# Power.net
KiCad netlist of a schematic drawn in Altium Designer
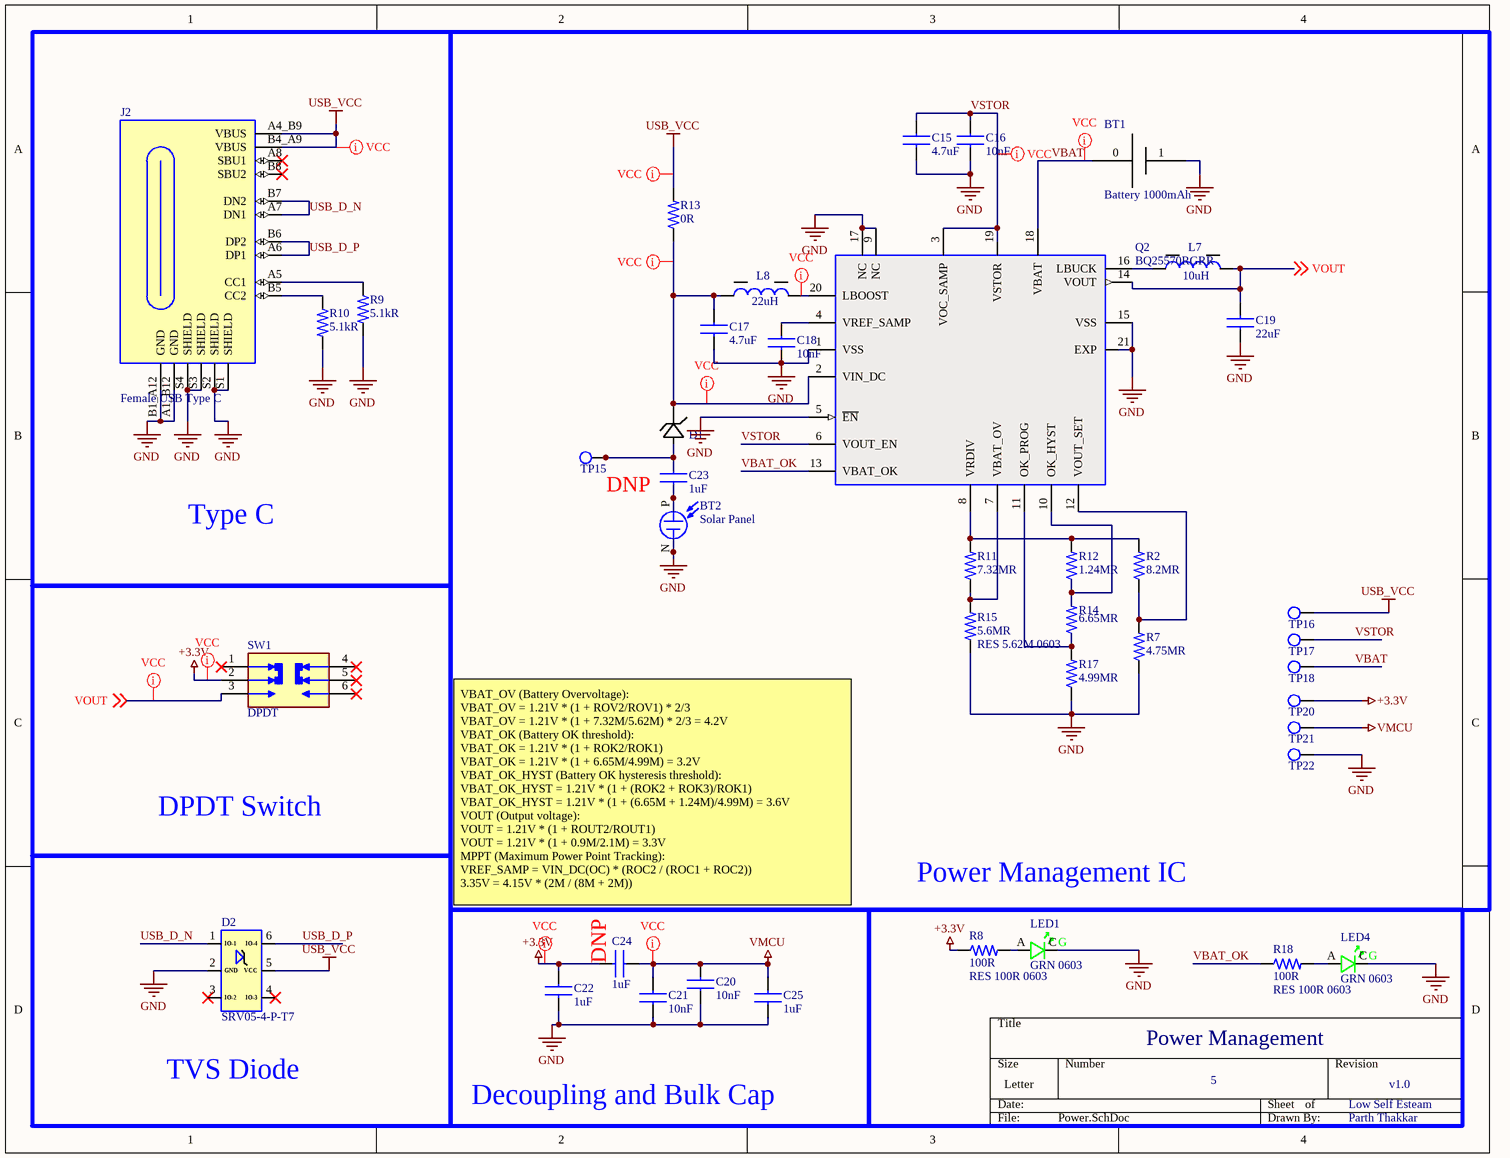
[diagram p0: Power.SchDoc]

(export (version "E")
  (design (tool "Eeschema 10.0.6"))
  (components
    (comp (ref "BT1")
      (value "Battery 1000mAh")
      (footprint "Battery")
      (description "Lithium Ion Polymer Battery - 3.7v 1200mAh ¦ Adafruit Industries 258")
      (fields
        (field (name "MANUFACTURER") "Adafruit Industries")
        (field (name "MANUFACTURER PART NUMBER") "258")
      )
      (libsource (lib "Keyboard_parts") (part "Battery 1000mAh"))
    )
    (comp (ref "BT2")
      (value "Solar Panel")
      (footprint "Solar panel")
      (description "Monocryst Solar Cell 184MW 4.15V")
      (fields (field (name "MANUFACTURER") "ANYSOLAR") (field (name "MANUFACTURER PART NUMBER") "SM141K06L"))
      (libsource (lib "Keyboard_parts") (part "Solar Panel"))
    )
    (comp (ref "C15")
      (value "4.7uF")
      (footprint "Capacitor 0603")
      (fields
        (field (name "MANUFACTURER") "Murata")
        (field (name "MANUFACTURER PART NUMBER") "GRT188R61E475KE13D")
        (field (name "Comment") "CAP 4.7uF 25V 0603")
      )
      (libsource (lib "Keyboard_parts") (part "CAP 4.7uF 25V 0603"))
    )
    (comp (ref "C16")
      (value "10nF")
      (footprint "Capacitor 0603")
      (fields
        (field (name "MANUFACTURER") "Murata")
        (field (name "MANUFACTURER PART NUMBER") "GCM188R72A103KA37D")
        (field (name "Comment") "CAP 10nF 100V 0603")
      )
      (libsource (lib "Keyboard_parts") (part "CAP 10nF 100V 0603"))
    )
    (comp (ref "C17")
      (value "4.7uF")
      (footprint "Capacitor 0603")
      (fields
        (field (name "MANUFACTURER") "Murata")
        (field (name "MANUFACTURER PART NUMBER") "GRT188R61E475KE13D")
        (field (name "Comment") "CAP 4.7uF 25V 0603")
      )
      (libsource (lib "Keyboard_parts") (part "CAP 4.7uF 25V 0603"))
    )
    (comp (ref "C18")
      (value "10nF")
      (footprint "Capacitor 0603")
      (fields
        (field (name "MANUFACTURER") "Murata")
        (field (name "MANUFACTURER PART NUMBER") "GCM188R72A103KA37D")
        (field (name "Comment") "CAP 10nF 100V 0603")
      )
      (libsource (lib "Keyboard_parts") (part "CAP 10nF 100V 0603"))
    )
    (comp (ref "C19")
      (value "22uF")
      (footprint "Capacitor 0603")
      (fields
        (field (name "MANUFACTURER") "Murata")
        (field (name "MANUFACTURER PART NUMBER") "GRM188R61A226ME15D")
        (field (name "TOLERANCE") "20 %")
      )
      (libsource (lib "Keyboard_parts") (part "CAP 22uF 6.3V 0603"))
    )
    (comp (ref "C20")
      (value "10nF")
      (footprint "Capacitor 0603")
      (fields
        (field (name "MANUFACTURER") "Murata")
        (field (name "MANUFACTURER PART NUMBER") "GCM188R72A103KA37D")
        (field (name "Comment") "CAP 0.1uF 100V 0603")
      )
      (libsource (lib "Keyboard_parts") (part "CAP 0.1uF 100V 0603"))
    )
    (comp (ref "C21")
      (value "10nF")
      (footprint "Capacitor 0603")
      (fields
        (field (name "MANUFACTURER") "Murata")
        (field (name "MANUFACTURER PART NUMBER") "GCM188R72A103KA37D")
        (field (name "Comment") "CAP 0.1uF 100V 0603")
      )
      (libsource (lib "Keyboard_parts") (part "CAP 0.1uF 100V 0603"))
    )
    (comp (ref "C22")
      (value "1uF")
      (footprint "CAPACITOR 0805")
      (description "Multilayer Ceramic Capacitor, 1 uF, 10 V, ± 20%, X5R, 0201 [0603 Metric]")
      (fields
        (field (name "MANUFACTURER") "Murata")
        (field (name "MANUFACTURER PART NUMBER") "GRM033R61A105ME15D")
      )
      (libsource (lib "Keyboard_parts") (part "CAP 47uF 10V 0805"))
    )
    (comp (ref "C23")
      (value "1uF")
      (footprint "CAPACITOR 0805")
      (description "Multilayer Ceramic Capacitor, 1 uF, 10 V, ± 20%, X5R, 0201 [0603 Metric]")
      (fields
        (field (name "MANUFACTURER") "Murata")
        (field (name "MANUFACTURER PART NUMBER") "GRM033R61A105ME15D")
      )
      (libsource (lib "Keyboard_parts") (part "CAP 47uF 10V 0805"))
    )
    (comp (ref "C24")
      (value "1uF")
      (footprint "CAPACITOR 0805")
      (description "Multilayer Ceramic Capacitor, 1 uF, 10 V, ± 20%, X5R, 0201 [0603 Metric]")
      (fields
        (field (name "MANUFACTURER") "Murata")
        (field (name "MANUFACTURER PART NUMBER") "GRM033R61A105ME15D")
      )
      (libsource (lib "Keyboard_parts") (part "CAP 47uF 10V 0805"))
    )
    (comp (ref "C25")
      (value "1uF")
      (footprint "CAPACITOR 0805")
      (description "Multilayer Ceramic Capacitor, 1 uF, 10 V, ± 20%, X5R, 0201 [0603 Metric]")
      (fields
        (field (name "MANUFACTURER") "Murata")
        (field (name "MANUFACTURER PART NUMBER") "GRM033R61A105ME15D")
      )
      (libsource (lib "Keyboard_parts") (part "CAP 47uF 10V 0805"))
    )
    (comp (ref "D1")
      (value "Diode Schottky")
      (footprint "Diode Schottky")
      (description "Rectifier Diode, Schottky, 2 Element, 0.2A, 30V V(RRM), Silicon")
      (fields (field (name "MANUFACTURER") "Good-Ark") (field (name "MANUFACTURER PART NUMBER") "BAT54C"))
      (libsource (lib "Keyboard_parts") (part "Diode Schottky"))
    )
    (comp (ref "D2")
      (value "SRV05-4-P-T7")
      (footprint "TVS")
      (description "Trans Voltage Suppressor Diode, 5V V(RWM), Unidirectional, 1 Element, Silicon")
      (fields (field (name "MANUFACTURER") "MCC") (field (name "MANUFACTURER PART NUMBER") "SRV05-4L-TP"))
      (libsource (lib "Keyboard_parts") (part "TVS_Diode"))
    )
    (comp (ref "J2")
      (value "Female USB Type C")
      (footprint "Type C")
      (fields (field (name "MANUFACTURER PART NUMBER") "USB4125-GF-A_REVA2"))
      (libsource (lib "Keyboard_parts") (part "USB-C Power Connector"))
    )
    (comp (ref "L7")
      (value "IND 10uH 1111")
      (footprint "IND 10uH (1x3.2)")
      (description "General Purpose Inductor, 10uH, 30%, 1 Element, Ferrite-Core, SMD, 1111")
      (fields
        (field (name "MANUFACTURER") "Wurth Electronics")
        (field (name "MANUFACTURER PART NUMBER") "744029100")
        (field (name "INDUCTANCE-NOM (L)") "10uH")
      )
      (libsource (lib "Keyboard_parts") (part "IND 10uH 1111"))
    )
    (comp (ref "L8")
      (value "IND 22uH 1515")
      (footprint "IND 22uH (1.6x4.3)")
      (description "General Purpose Inductor, 22uH, 30%, 1 Element, Ferrite-Core, SMD, 1515")
      (fields
        (field (name "MANUFACTURER") "Wurth Electronics")
        (field (name "MANUFACTURER PART NUMBER") "744031220")
        (field (name "INDUCTANCE-NOM (L)") "22uH")
      )
      (libsource (lib "Keyboard_parts") (part "IND 22uH 1515"))
    )
    (comp (ref "LED1")
      (value "GRN 0603")
      (footprint "LED 0603")
      (description "LED, 0603, GREEN, 430MCD, 520NM")
      (fields
        (field (name "MANUFACTURER") "Wurth Electronics")
        (field (name "MANUFACTURER PART NUMBER") "150060GS75000")
      )
      (libsource (lib "Keyboard_parts") (part "LED Green 0603"))
    )
    (comp (ref "LED4")
      (value "GRN 0603")
      (footprint "LED 0603")
      (description "LED, 0603, GREEN, 430MCD, 520NM")
      (fields
        (field (name "MANUFACTURER") "Wurth Electronics")
        (field (name "MANUFACTURER PART NUMBER") "150060GS75000")
      )
      (libsource (lib "Keyboard_parts") (part "LED Green 0603"))
    )
    (comp (ref "Q2")
      (value "BQ25570RGRR")
      (footprint "BQ25570RGRR")
      (description "Power Supply Support Circuit, Adjustable, 1 Channel, PQCC20")
      (fields (field (name "MANUFACTURER") "Texas Instruments"))
      (libsource (lib "Keyboard_parts") (part "BQ25570RGRR"))
    )
    (comp (ref "R2")
      (value "8.2MR")
      (footprint "Resistor 0603")
      (fields
        (field (name "MANUFACTURER") "Yageo")
        (field (name "MANUFACTURER PART NUMBER") "RC0603JR-078M2L")
        (field (name "TOLERANCE") "5%")
      )
      (libsource (lib "Keyboard_parts") (part "RES 8.2M 0603"))
    )
    (comp (ref "R7")
      (value "4.75MR")
      (footprint "Resistor 0603")
      (fields
        (field (name "MANUFACTURER") "Yageo")
        (field (name "MANUFACTURER PART NUMBER") "RC0603FR-074M75L")
        (field (name "TOLERANCE") "1%")
      )
      (libsource (lib "Keyboard_parts") (part "RES 4.75M 0603"))
    )
    (comp (ref "R8")
      (value "RES 100R 0603")
      (footprint "Resistor 0603")
      (fields
        (field (name "MANUFACTURER") "Yageo")
        (field (name "MANUFACTURER PART NUMBER") "RC0603FR-07100RL")
        (field (name "TOLERANCE") "1%")
        (field (name "ALTIUM_VALUE") "100R")
      )
      (libsource (lib "Keyboard_parts") (part "RES 100R 0603"))
    )
    (comp (ref "R9")
      (value "5.1kR")
      (footprint "Resistor 0603")
      (fields
        (field (name "MANUFACTURER") "Yageo")
        (field (name "MANUFACTURER PART NUMBER") "RC0603FR-075K1L")
        (field (name "TOLERANCE") "1%")
      )
      (libsource (lib "Keyboard_parts") (part "RES 5.1K 0603"))
    )
    (comp (ref "R10")
      (value "5.1kR")
      (footprint "Resistor 0603")
      (fields
        (field (name "MANUFACTURER") "Yageo")
        (field (name "MANUFACTURER PART NUMBER") "RC0603FR-075K1L")
        (field (name "TOLERANCE") "1%")
      )
      (libsource (lib "Keyboard_parts") (part "RES 5.1K 0603"))
    )
    (comp (ref "R11")
      (value "7.32MR")
      (footprint "Resistor 0603")
      (fields
        (field (name "MANUFACTURER") "Yageo")
        (field (name "MANUFACTURER PART NUMBER") "RC0402FR-077M32L")
        (field (name "TOLERANCE") "1%")
      )
      (libsource (lib "Keyboard_parts") (part "RES 7.32M 0603"))
    )
    (comp (ref "R12")
      (value "1.24MR")
      (footprint "Resistor 0603")
      (fields
        (field (name "MANUFACTURER") "Yageo")
        (field (name "MANUFACTURER PART NUMBER") "RC0603FR-071M24L")
        (field (name "TOLERANCE") "1%")
      )
      (libsource (lib "Keyboard_parts") (part "RES 1.24M 0603"))
    )
    (comp (ref "R13")
      (value "0R")
      (footprint "Resistor 0402")
      (description "Metal Glaze/thick Film, 0.0625W, 0ohm, Surface Mount, 0402")
      (fields
        (field (name "MANUFACTURER") "Yageo")
        (field (name "MANUFACTURER PART NUMBER") "RC0402JR-070RL")
      )
      (libsource (lib "Keyboard_parts") (part "RES 0R 0402"))
    )
    (comp (ref "R14")
      (value "6.65MR")
      (footprint "Resistor 0603")
      (fields
        (field (name "MANUFACTURER") "Vishay")
        (field (name "MANUFACTURER PART NUMBER") "CRCW06036M65FKEA")
        (field (name "TOLERANCE") "1%")
      )
      (libsource (lib "Keyboard_parts") (part "RES 6.65M 0603"))
    )
    (comp (ref "R15")
      (value "RES 5.62M 0603")
      (footprint "Resistor 0603")
      (fields
        (field (name "MANUFACTURER") "Yageo")
        (field (name "MANUFACTURER PART NUMBER") "RC0603JR-075M6L")
        (field (name "TOLERANCE") "5%")
        (field (name "ALTIUM_VALUE") "5.6MR")
      )
      (libsource (lib "Keyboard_parts") (part "RES 5.62M 0603"))
    )
    (comp (ref "R17")
      (value "4.99MR")
      (footprint "Resistor 0603")
      (fields
        (field (name "MANUFACTURER") "Yageo")
        (field (name "MANUFACTURER PART NUMBER") "RC0603FR-074M99L")
        (field (name "TOLERANCE") "1%")
      )
      (libsource (lib "Keyboard_parts") (part "RES 4.99M 0603"))
    )
    (comp (ref "R18")
      (value "RES 100R 0603")
      (footprint "Resistor 0603")
      (fields
        (field (name "MANUFACTURER") "Yageo")
        (field (name "MANUFACTURER PART NUMBER") "RC0603FR-07100RL")
        (field (name "TOLERANCE") "1%")
        (field (name "ALTIUM_VALUE") "100R")
      )
      (libsource (lib "Keyboard_parts") (part "RES 100R 0603"))
    )
    (comp (ref "SW1")
      (value "DPDT")
      (footprint "DPDT")
      (description "Slide Switch, DPDT, Latched, Solder Terminal, Through Hole-right Angle")
      (fields (field (name "MANUFACTURER") "E-Switch") (field (name "MANUFACTURER PART NUMBER") "EG2208"))
      (libsource (lib "Keyboard_parts") (part "DPDT"))
    )
    (comp (ref "TP15")
      (value "Test point")
      (footprint "Test Point")
      (libsource (lib "Keyboard_parts") (part "Test point"))
    )
    (comp (ref "TP16")
      (value "Test point")
      (footprint "Test Point")
      (libsource (lib "Keyboard_parts") (part "Test point"))
    )
    (comp (ref "TP17")
      (value "Test point")
      (footprint "Test Point")
      (libsource (lib "Keyboard_parts") (part "Test point"))
    )
    (comp (ref "TP18")
      (value "Test point")
      (footprint "Test Point")
      (libsource (lib "Keyboard_parts") (part "Test point"))
    )
    (comp (ref "TP20")
      (value "Test point")
      (footprint "Test Point")
      (libsource (lib "Keyboard_parts") (part "Test point"))
    )
    (comp (ref "TP21")
      (value "Test point")
      (footprint "Test Point")
      (libsource (lib "Keyboard_parts") (part "Test point"))
    )
    (comp (ref "TP22")
      (value "Test point")
      (footprint "Test Point")
      (libsource (lib "Keyboard_parts") (part "Test point"))
    )
  )
  (nets
    (net (code "1") (name "+3.3V") (class "Default")
      (node (ref "C22") (pin "1") (pinfunction "1_1") (pintype "passive"))
      (node (ref "C24") (pin "1") (pinfunction "1_1") (pintype "passive"))
      (node (ref "R8") (pin "1") (pinfunction "1_1") (pintype "passive"))
      (node (ref "SW1") (pin "2") (pinfunction "2_2") (pintype "passive"))
      (node (ref "TP20") (pin "1") (pinfunction "1_1") (pintype "passive"))
    )
    (net (code "2") (name "/USB_D_N") (class "Default")
      (node (ref "D2") (pin "1") (pinfunction "IO-1_1") (pintype "passive"))
      (node (ref "J2") (pin "A7") (pinfunction "DN1_A7") (pintype "bidirectional"))
      (node (ref "J2") (pin "B7") (pinfunction "DN2_B7") (pintype "bidirectional"))
    )
    (net (code "3") (name "/USB_D_P") (class "Default")
      (node (ref "D2") (pin "6") (pinfunction "IO-4_6") (pintype "passive"))
      (node (ref "J2") (pin "A6") (pinfunction "DP1_A6") (pintype "bidirectional"))
      (node (ref "J2") (pin "B6") (pinfunction "DP2_B6") (pintype "bidirectional"))
    )
    (net (code "4") (name "/VBAT") (class "Default")
      (node (ref "BT1") (pin "0") (pinfunction "VCC_0") (pintype "passive"))
      (node (ref "Q2") (pin "18") (pinfunction "VBAT_18") (pintype "power_in"))
      (node (ref "TP18") (pin "1") (pinfunction "1_1") (pintype "passive"))
    )
    (net (code "5") (name "/VBAT_OK") (class "Default")
      (node (ref "Q2") (pin "13") (pinfunction "VBAT_OK_13") (pintype "passive"))
      (node (ref "R18") (pin "1") (pinfunction "1_1") (pintype "passive"))
    )
    (net (code "6") (name "/VSTOR") (class "Default")
      (node (ref "C15") (pin "1") (pinfunction "1_1") (pintype "passive"))
      (node (ref "C16") (pin "1") (pinfunction "1_1") (pintype "passive"))
      (node (ref "Q2") (pin "19") (pinfunction "VSTOR_19") (pintype "passive"))
      (node (ref "Q2") (pin "3") (pinfunction "VOC_SAMP_3") (pintype "passive"))
      (node (ref "Q2") (pin "6") (pinfunction "VOUT_EN_6") (pintype "passive"))
      (node (ref "TP17") (pin "1") (pinfunction "1_1") (pintype "passive"))
    )
    (net (code "7") (name "GND") (class "Default")
      (node (ref "BT1") (pin "1") (pinfunction "GND_1") (pintype "passive"))
      (node (ref "BT2") (pin "N") (pinfunction "N_N") (pintype "passive"))
      (node (ref "C15") (pin "2") (pinfunction "2_2") (pintype "passive"))
      (node (ref "C16") (pin "2") (pinfunction "2_2") (pintype "passive"))
      (node (ref "C17") (pin "2") (pinfunction "2_2") (pintype "passive"))
      (node (ref "C18") (pin "1") (pinfunction "1_1") (pintype "passive"))
      (node (ref "C19") (pin "2") (pinfunction "2_2") (pintype "passive"))
      (node (ref "C20") (pin "2") (pinfunction "2_2") (pintype "passive"))
      (node (ref "C21") (pin "2") (pinfunction "2_2") (pintype "passive"))
      (node (ref "C22") (pin "2") (pinfunction "2_2") (pintype "passive"))
      (node (ref "C25") (pin "2") (pinfunction "2_2") (pintype "passive"))
      (node (ref "D2") (pin "2") (pinfunction "GND_2") (pintype "passive"))
      (node (ref "J2") (pin "A1_B12") (pinfunction "GND_A1_B12") (pintype "power_in"))
      (node (ref "J2") (pin "B1_A12") (pinfunction "GND_B1_A12") (pintype "power_in"))
      (node (ref "J2") (pin "S1") (pinfunction "SHIELD_S1") (pintype "passive"))
      (node (ref "J2") (pin "S2") (pinfunction "SHIELD_S2") (pintype "passive"))
      (node (ref "J2") (pin "S3") (pinfunction "SHIELD_S3") (pintype "passive"))
      (node (ref "J2") (pin "S4") (pinfunction "SHIELD_S4") (pintype "passive"))
      (node (ref "LED1") (pin "C") (pinfunction "C_C") (pintype "passive"))
      (node (ref "LED4") (pin "C") (pinfunction "C_C") (pintype "passive"))
      (node (ref "Q2") (pin "1") (pinfunction "VSS_1") (pintype "passive"))
      (node (ref "Q2") (pin "15") (pinfunction "VSS_15") (pintype "passive"))
      (node (ref "Q2") (pin "17") (pinfunction "NC_17") (pintype "passive"))
      (node (ref "Q2") (pin "21") (pinfunction "EXP_21") (pintype "passive"))
      (node (ref "Q2") (pin "5") (pinfunction "~{EN}_5") (pintype "input"))
      (node (ref "Q2") (pin "9") (pinfunction "NC_9") (pintype "passive"))
      (node (ref "R10") (pin "2") (pinfunction "2_2") (pintype "passive"))
      (node (ref "R15") (pin "1") (pinfunction "1_1") (pintype "passive"))
      (node (ref "R17") (pin "1") (pinfunction "1_1") (pintype "passive"))
      (node (ref "R7") (pin "1") (pinfunction "1_1") (pintype "passive"))
      (node (ref "R9") (pin "2") (pinfunction "2_2") (pintype "passive"))
      (node (ref "TP22") (pin "1") (pinfunction "1_1") (pintype "passive"))
    )
    (net (code "8") (name "Net-(BT2-PadP)") (class "Default")
      (node (ref "BT2") (pin "P") (pinfunction "P_P") (pintype "passive"))
      (node (ref "C23") (pin "2") (pinfunction "2_2") (pintype "passive"))
    )
    (net (code "9") (name "Net-(C23-Pad1)") (class "Default")
      (node (ref "C23") (pin "1") (pinfunction "1_1") (pintype "passive"))
      (node (ref "D1") (pin "1") (pinfunction "1_1") (pintype "passive"))
      (node (ref "TP15") (pin "1") (pinfunction "1_1") (pintype "passive"))
    )
    (net (code "10") (name "Net-(J2-CC1)") (class "Default")
      (node (ref "J2") (pin "A5") (pinfunction "CC1_A5") (pintype "bidirectional"))
      (node (ref "R9") (pin "1") (pinfunction "1_1") (pintype "passive"))
    )
    (net (code "11") (name "Net-(J2-CC2)") (class "Default")
      (node (ref "J2") (pin "B5") (pinfunction "CC2_B5") (pintype "bidirectional"))
      (node (ref "R10") (pin "1") (pinfunction "1_1") (pintype "passive"))
    )
    (net (code "12") (name "Net-(LED1-PadA)") (class "Default")
      (node (ref "LED1") (pin "A") (pinfunction "A_A") (pintype "passive"))
      (node (ref "R8") (pin "2") (pinfunction "2_2") (pintype "passive"))
    )
    (net (code "13") (name "Net-(LED4-PadA)") (class "Default")
      (node (ref "LED4") (pin "A") (pinfunction "A_A") (pintype "passive"))
      (node (ref "R18") (pin "2") (pinfunction "2_2") (pintype "passive"))
    )
    (net (code "14") (name "Net-(Q2-LBOOST)") (class "Default")
      (node (ref "L8") (pin "2") (pinfunction "2_2") (pintype "passive"))
      (node (ref "Q2") (pin "20") (pinfunction "LBOOST_20") (pintype "power_in"))
    )
    (net (code "15") (name "Net-(Q2-LBUCK)") (class "Default")
      (node (ref "L7") (pin "1") (pinfunction "1_1") (pintype "passive"))
      (node (ref "Q2") (pin "16") (pinfunction "LBUCK_16") (pintype "power_in"))
    )
    (net (code "16") (name "Net-(Q2-OK_HYST)") (class "Default")
      (node (ref "Q2") (pin "10") (pinfunction "OK_HYST_10") (pintype "power_in"))
      (node (ref "R12") (pin "1") (pinfunction "1_1") (pintype "passive"))
      (node (ref "R14") (pin "2") (pinfunction "2_2") (pintype "passive"))
    )
    (net (code "17") (name "Net-(Q2-OK_PROG)") (class "Default")
      (node (ref "Q2") (pin "11") (pinfunction "OK_PROG_11") (pintype "power_in"))
      (node (ref "R14") (pin "1") (pinfunction "1_1") (pintype "passive"))
      (node (ref "R17") (pin "2") (pinfunction "2_2") (pintype "passive"))
    )
    (net (code "18") (name "Net-(Q2-VBAT_OV)") (class "Default")
      (node (ref "Q2") (pin "7") (pinfunction "VBAT_OV_7") (pintype "passive"))
      (node (ref "R11") (pin "1") (pinfunction "1_1") (pintype "passive"))
      (node (ref "R15") (pin "2") (pinfunction "2_2") (pintype "passive"))
    )
    (net (code "19") (name "Net-(Q2-VIN_DC)") (class "Default")
      (node (ref "C17") (pin "1") (pinfunction "1_1") (pintype "passive"))
      (node (ref "D1") (pin "3") (pinfunction "3_3") (pintype "passive"))
      (node (ref "L8") (pin "1") (pinfunction "1_1") (pintype "passive"))
      (node (ref "Q2") (pin "2") (pinfunction "VIN_DC_2") (pintype "passive"))
      (node (ref "R13") (pin "1") (pinfunction "1_1") (pintype "passive"))
    )
    (net (code "20") (name "Net-(Q2-VOUT_SET)") (class "Default")
      (node (ref "Q2") (pin "12") (pinfunction "VOUT_SET_12") (pintype "passive"))
      (node (ref "R2") (pin "1") (pinfunction "1_1") (pintype "passive"))
      (node (ref "R7") (pin "2") (pinfunction "2_2") (pintype "passive"))
    )
    (net (code "21") (name "Net-(Q2-VRDIV)") (class "Default")
      (node (ref "Q2") (pin "8") (pinfunction "VRDIV_8") (pintype "passive"))
      (node (ref "R11") (pin "2") (pinfunction "2_2") (pintype "passive"))
      (node (ref "R12") (pin "2") (pinfunction "2_2") (pintype "passive"))
      (node (ref "R2") (pin "2") (pinfunction "2_2") (pintype "passive"))
    )
    (net (code "22") (name "Net-(Q2-VREF_SAMP)") (class "Default")
      (node (ref "C18") (pin "2") (pinfunction "2_2") (pintype "passive"))
      (node (ref "Q2") (pin "4") (pinfunction "VREF_SAMP_4") (pintype "passive"))
    )
    (net (code "23") (name "USB_VCC") (class "Default")
      (node (ref "D2") (pin "5") (pinfunction "VCC_5") (pintype "passive"))
      (node (ref "J2") (pin "A4_B9") (pinfunction "VBUS_A4_B9") (pintype "power_in"))
      (node (ref "J2") (pin "B4_A9") (pinfunction "VBUS_B4_A9") (pintype "power_in"))
      (node (ref "R13") (pin "2") (pinfunction "2_2") (pintype "passive"))
      (node (ref "TP16") (pin "1") (pinfunction "1_1") (pintype "passive"))
    )
    (net (code "24") (name "VMCU") (class "Default")
      (node (ref "C20") (pin "1") (pinfunction "1_1") (pintype "passive"))
      (node (ref "C21") (pin "1") (pinfunction "1_1") (pintype "passive"))
      (node (ref "C24") (pin "2") (pinfunction "2_2") (pintype "passive"))
      (node (ref "C25") (pin "1") (pinfunction "1_1") (pintype "passive"))
      (node (ref "TP21") (pin "1") (pinfunction "1_1") (pintype "passive"))
    )
    (net (code "25") (name "VOUT") (class "Default")
      (node (ref "C19") (pin "1") (pinfunction "1_1") (pintype "passive"))
      (node (ref "L7") (pin "2") (pinfunction "2_2") (pintype "passive"))
      (node (ref "Q2") (pin "14") (pinfunction "VOUT_14") (pintype "output"))
      (node (ref "SW1") (pin "3") (pinfunction "3_3") (pintype "passive"))
    )
    (net (code "26") (name "unconnected-(D2-IO-2-Pad3)") (class "Default")
      (node (ref "D2") (pin "3") (pinfunction "IO-2_3") (pintype "passive+no_connect"))
    )
    (net (code "27") (name "unconnected-(D2-IO-3-Pad4)") (class "Default")
      (node (ref "D2") (pin "4") (pinfunction "IO-3_4") (pintype "passive+no_connect"))
    )
    (net (code "28") (name "unconnected-(J2-SBU1-PadA8)") (class "Default")
      (node (ref "J2") (pin "A8") (pinfunction "SBU1_A8") (pintype "bidirectional+no_connect"))
    )
    (net (code "29") (name "unconnected-(J2-SBU2-PadB8)") (class "Default")
      (node (ref "J2") (pin "B8") (pinfunction "SBU2_B8") (pintype "bidirectional+no_connect"))
    )
    (net (code "30") (name "unconnected-(SW1-Pad1)") (class "Default")
      (node (ref "SW1") (pin "1") (pinfunction "1_1") (pintype "passive+no_connect"))
    )
    (net (code "31") (name "unconnected-(SW1-Pad4)") (class "Default")
      (node (ref "SW1") (pin "4") (pinfunction "4_4") (pintype "passive+no_connect"))
    )
    (net (code "32") (name "unconnected-(SW1-Pad5)") (class "Default")
      (node (ref "SW1") (pin "5") (pinfunction "5_5") (pintype "passive+no_connect"))
    )
    (net (code "33") (name "unconnected-(SW1-Pad6)") (class "Default")
      (node (ref "SW1") (pin "6") (pinfunction "6_6") (pintype "passive+no_connect"))
    )
  )
)
